# Sheet1.net
KiCad netlist of a schematic drawn in Altium Designer
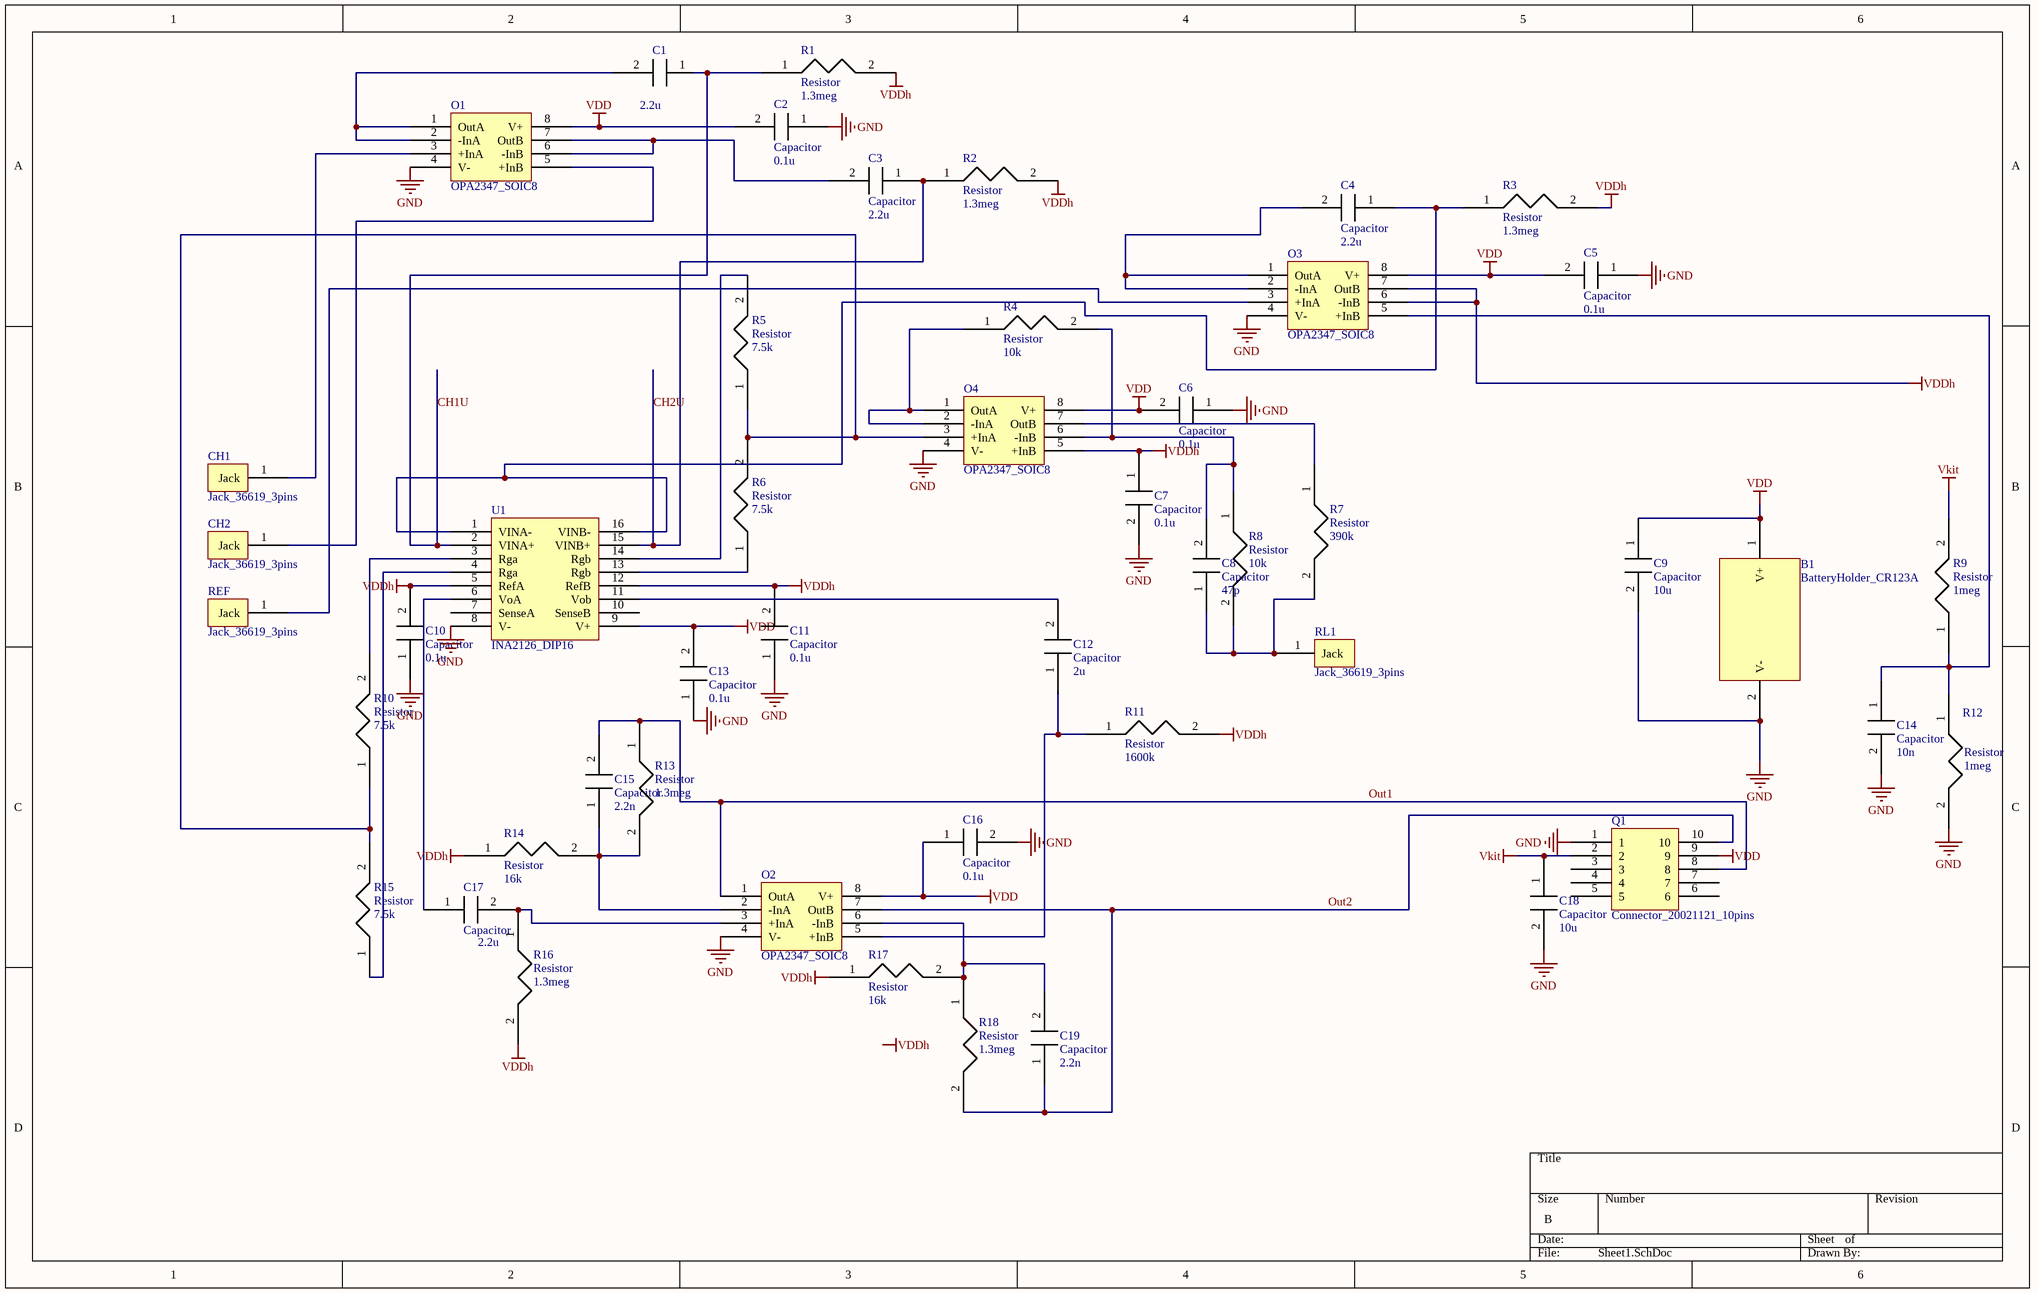
[diagram p0: Sheet1.SchDoc]

(export (version "E")
  (design (tool "Eeschema 10.0.6"))
  (components
    (comp (ref "B1")
      (value "BatteryHolder_CR123A")
      (footprint "BatterHolder_CR123A")
      (libsource (lib "Schlib1") (part "BatteryHolder_CR123A"))
    )
    (comp (ref "C1")
      (value "2.2u")
      (footprint "Capacitor")
      (fields (field (name "Comment") "Capacitor"))
      (libsource (lib "Schlib1") (part "Capacitor"))
    )
    (comp (ref "C2")
      (value "Capacitor")
      (footprint "Capacitor")
      (fields (field (name "ALTIUM_VALUE") "0.1u"))
      (libsource (lib "Schlib1") (part "Capacitor"))
    )
    (comp (ref "C3")
      (value "Capacitor")
      (footprint "Capacitor")
      (fields (field (name "ALTIUM_VALUE") "2.2u"))
      (libsource (lib "Schlib1") (part "Capacitor"))
    )
    (comp (ref "C4")
      (value "Capacitor")
      (footprint "Capacitor")
      (fields (field (name "ALTIUM_VALUE") "2.2u"))
      (libsource (lib "Schlib1") (part "Capacitor"))
    )
    (comp (ref "C5")
      (value "Capacitor")
      (footprint "Capacitor")
      (fields (field (name "ALTIUM_VALUE") "0.1u"))
      (libsource (lib "Schlib1") (part "Capacitor"))
    )
    (comp (ref "C6")
      (value "Capacitor")
      (footprint "Capacitor")
      (fields (field (name "ALTIUM_VALUE") "0.1u"))
      (libsource (lib "Schlib1") (part "Capacitor"))
    )
    (comp (ref "C7")
      (value "Capacitor")
      (footprint "Capacitor")
      (fields (field (name "ALTIUM_VALUE") "0.1u"))
      (libsource (lib "Schlib1") (part "Capacitor"))
    )
    (comp (ref "C8")
      (value "Capacitor")
      (footprint "Capacitor")
      (fields (field (name "ALTIUM_VALUE") "47p"))
      (libsource (lib "Schlib1") (part "Capacitor"))
    )
    (comp (ref "C9")
      (value "Capacitor")
      (footprint "Capacitor")
      (fields (field (name "ALTIUM_VALUE") "10u"))
      (libsource (lib "Schlib1") (part "Capacitor"))
    )
    (comp (ref "C10")
      (value "Capacitor")
      (footprint "Capacitor")
      (fields (field (name "ALTIUM_VALUE") "0.1u"))
      (libsource (lib "Schlib1") (part "Capacitor"))
    )
    (comp (ref "C11")
      (value "Capacitor")
      (footprint "Capacitor")
      (fields (field (name "ALTIUM_VALUE") "0.1u"))
      (libsource (lib "Schlib1") (part "Capacitor"))
    )
    (comp (ref "C12")
      (value "Capacitor")
      (footprint "Capacitor")
      (fields (field (name "ALTIUM_VALUE") "2u"))
      (libsource (lib "Schlib1") (part "Capacitor"))
    )
    (comp (ref "C13")
      (value "Capacitor")
      (footprint "Capacitor")
      (fields (field (name "ALTIUM_VALUE") "0.1u"))
      (libsource (lib "Schlib1") (part "Capacitor"))
    )
    (comp (ref "C14")
      (value "Capacitor")
      (footprint "Capacitor")
      (fields (field (name "ALTIUM_VALUE") "10n"))
      (libsource (lib "Schlib1") (part "Capacitor"))
    )
    (comp (ref "C15")
      (value "Capacitor")
      (footprint "Capacitor")
      (fields (field (name "ALTIUM_VALUE") "2.2n"))
      (libsource (lib "Schlib1") (part "Capacitor"))
    )
    (comp (ref "C16")
      (value "Capacitor")
      (footprint "Capacitor")
      (fields (field (name "ALTIUM_VALUE") "0.1u"))
      (libsource (lib "Schlib1") (part "Capacitor"))
    )
    (comp (ref "C17")
      (value "Capacitor")
      (footprint "Capacitor")
      (fields (field (name "ALTIUM_VALUE") "2.2u"))
      (libsource (lib "Schlib1") (part "Capacitor"))
    )
    (comp (ref "C18")
      (value "Capacitor")
      (footprint "Capacitor")
      (fields (field (name "ALTIUM_VALUE") "10u"))
      (libsource (lib "Schlib1") (part "Capacitor"))
    )
    (comp (ref "C19")
      (value "Capacitor")
      (footprint "Capacitor")
      (fields (field (name "ALTIUM_VALUE") "2.2n"))
      (libsource (lib "Schlib1") (part "Capacitor"))
    )
    (comp (ref "CH1")
      (value "Jack_36619_3pins")
      (footprint "Jack_36619_3pads")
      (libsource (lib "Schlib1") (part "Jack_36619_3pins"))
    )
    (comp (ref "CH2")
      (value "Jack_36619_3pins")
      (footprint "Jack_36619_3pads")
      (libsource (lib "Schlib1") (part "Jack_36619_3pins"))
    )
    (comp (ref "O1")
      (value "OPA2347_SOIC8")
      (footprint "OPA2347P_SOIC8")
      (libsource (lib "Schlib1") (part "OPA2347_SOIC8"))
    )
    (comp (ref "O2")
      (value "OPA2347_SOIC8")
      (footprint "OPA2347P_SOIC8")
      (libsource (lib "Schlib1") (part "OPA2347_SOIC8"))
    )
    (comp (ref "O3")
      (value "OPA2347_SOIC8")
      (footprint "OPA2347P_SOIC8")
      (libsource (lib "Schlib1") (part "OPA2347_SOIC8"))
    )
    (comp (ref "O4")
      (value "OPA2347_SOIC8")
      (footprint "OPA2347P_SOIC8")
      (libsource (lib "Schlib1") (part "OPA2347_SOIC8"))
    )
    (comp (ref "Q1")
      (value "Connector_20021121_10pins")
      (footprint "20021121-10pins")
      (libsource (lib "Schlib1") (part "Connector_20021121_10pins"))
    )
    (comp (ref "R1")
      (value "Resistor")
      (footprint "Resisitor")
      (fields (field (name "ALTIUM_VALUE") "1.3meg"))
      (libsource (lib "Schlib1") (part "Resistor"))
    )
    (comp (ref "R2")
      (value "Resistor")
      (footprint "Resisitor")
      (fields (field (name "ALTIUM_VALUE") "1.3meg"))
      (libsource (lib "Schlib1") (part "Resistor"))
    )
    (comp (ref "R3")
      (value "Resistor")
      (footprint "Resisitor")
      (fields (field (name "ALTIUM_VALUE") "1.3meg"))
      (libsource (lib "Schlib1") (part "Resistor"))
    )
    (comp (ref "R4")
      (value "Resistor")
      (footprint "Resisitor")
      (fields (field (name "ALTIUM_VALUE") "10k"))
      (libsource (lib "Schlib1") (part "Resistor"))
    )
    (comp (ref "R5")
      (value "Resistor")
      (footprint "Resisitor")
      (fields (field (name "ALTIUM_VALUE") "7.5k"))
      (libsource (lib "Schlib1") (part "Resistor"))
    )
    (comp (ref "R6")
      (value "Resistor")
      (footprint "Resisitor")
      (fields (field (name "ALTIUM_VALUE") "7.5k"))
      (libsource (lib "Schlib1") (part "Resistor"))
    )
    (comp (ref "R7")
      (value "Resistor")
      (footprint "Resisitor")
      (fields (field (name "ALTIUM_VALUE") "390k"))
      (libsource (lib "Schlib1") (part "Resistor"))
    )
    (comp (ref "R8")
      (value "Resistor")
      (footprint "Resisitor")
      (fields (field (name "ALTIUM_VALUE") "10k"))
      (libsource (lib "Schlib1") (part "Resistor"))
    )
    (comp (ref "R9")
      (value "Resistor")
      (footprint "Resisitor")
      (fields (field (name "ALTIUM_VALUE") "1meg"))
      (libsource (lib "Schlib1") (part "Resistor"))
    )
    (comp (ref "R10")
      (value "Resistor")
      (footprint "Resisitor")
      (fields (field (name "ALTIUM_VALUE") "7.5k"))
      (libsource (lib "Schlib1") (part "Resistor"))
    )
    (comp (ref "R11")
      (value "Resistor")
      (footprint "Resisitor")
      (fields (field (name "ALTIUM_VALUE") "1600k"))
      (libsource (lib "Schlib1") (part "Resistor"))
    )
    (comp (ref "R12")
      (value "Resistor")
      (footprint "Resisitor")
      (fields (field (name "ALTIUM_VALUE") "1meg"))
      (libsource (lib "Schlib1") (part "Resistor"))
    )
    (comp (ref "R13")
      (value "Resistor")
      (footprint "Resisitor")
      (fields (field (name "ALTIUM_VALUE") "1.3meg"))
      (libsource (lib "Schlib1") (part "Resistor"))
    )
    (comp (ref "R14")
      (value "Resistor")
      (footprint "Resisitor")
      (fields (field (name "ALTIUM_VALUE") "16k"))
      (libsource (lib "Schlib1") (part "Resistor"))
    )
    (comp (ref "R15")
      (value "Resistor")
      (footprint "Resisitor")
      (fields (field (name "ALTIUM_VALUE") "7.5k"))
      (libsource (lib "Schlib1") (part "Resistor"))
    )
    (comp (ref "R16")
      (value "Resistor")
      (footprint "Resisitor")
      (fields (field (name "ALTIUM_VALUE") "1.3meg"))
      (libsource (lib "Schlib1") (part "Resistor"))
    )
    (comp (ref "R17")
      (value "Resistor")
      (footprint "Resisitor")
      (fields (field (name "ALTIUM_VALUE") "16k"))
      (libsource (lib "Schlib1") (part "Resistor"))
    )
    (comp (ref "R18")
      (value "Resistor")
      (footprint "Resisitor")
      (fields (field (name "ALTIUM_VALUE") "1.3meg"))
      (libsource (lib "Schlib1") (part "Resistor"))
    )
    (comp (ref "REF")
      (value "Jack_36619_3pins")
      (footprint "Jack_36619_3pads")
      (libsource (lib "Schlib1") (part "Jack_36619_3pins"))
    )
    (comp (ref "RL1")
      (value "Jack_36619_3pins")
      (footprint "Jack_36619_3pads")
      (libsource (lib "") (part "Jack_36619_3pins_1"))
    )
    (comp (ref "U1")
      (value "INA2126_DIP16")
      (footprint "INA2126_DIP16")
      (libsource (lib "Schlib1") (part "INA2126_DIP16"))
    )
  )
  (nets
    (net (code "1") (name "/CH1U") (class "Default")
      (node (ref "C1") (pin "1") (pinfunction "V-_1") (pintype "passive"))
      (node (ref "R1") (pin "1") (pinfunction "V-_1") (pintype "passive"))
      (node (ref "U1") (pin "2") (pinfunction "VINA+_2") (pintype "passive"))
    )
    (net (code "2") (name "/CH2U") (class "Default")
      (node (ref "C3") (pin "1") (pinfunction "V-_1") (pintype "passive"))
      (node (ref "R2") (pin "1") (pinfunction "V-_1") (pintype "passive"))
      (node (ref "U1") (pin "15") (pinfunction "VINB+_15") (pintype "passive"))
    )
    (net (code "3") (name "/Out1") (class "Default")
      (node (ref "C15") (pin "2") (pinfunction "V-_2") (pintype "passive"))
      (node (ref "O2") (pin "1") (pinfunction "OutA_1") (pintype "passive"))
      (node (ref "Q1") (pin "8") (pinfunction "8_8") (pintype "passive"))
      (node (ref "R13") (pin "1") (pinfunction "V-_1") (pintype "passive"))
    )
    (net (code "4") (name "/Out2") (class "Default")
      (node (ref "C19") (pin "1") (pinfunction "V-_1") (pintype "passive"))
      (node (ref "O2") (pin "7") (pinfunction "OutB_7") (pintype "passive"))
      (node (ref "Q1") (pin "10") (pinfunction "10_10") (pintype "passive"))
      (node (ref "R18") (pin "2") (pinfunction "V-_2") (pintype "passive"))
    )
    (net (code "5") (name "GND") (class "Default")
      (node (ref "B1") (pin "2") (pinfunction "V-_2") (pintype "passive"))
      (node (ref "C10") (pin "1") (pinfunction "V-_1") (pintype "passive"))
      (node (ref "C11") (pin "1") (pinfunction "V-_1") (pintype "passive"))
      (node (ref "C13") (pin "1") (pinfunction "V-_1") (pintype "passive"))
      (node (ref "C14") (pin "2") (pinfunction "V-_2") (pintype "passive"))
      (node (ref "C16") (pin "2") (pinfunction "V-_2") (pintype "passive"))
      (node (ref "C18") (pin "2") (pinfunction "V-_2") (pintype "passive"))
      (node (ref "C2") (pin "1") (pinfunction "V-_1") (pintype "passive"))
      (node (ref "C5") (pin "1") (pinfunction "V-_1") (pintype "passive"))
      (node (ref "C6") (pin "1") (pinfunction "V-_1") (pintype "passive"))
      (node (ref "C7") (pin "2") (pinfunction "V-_2") (pintype "passive"))
      (node (ref "C9") (pin "2") (pinfunction "V-_2") (pintype "passive"))
      (node (ref "O1") (pin "4") (pinfunction "V-_4") (pintype "passive"))
      (node (ref "O2") (pin "4") (pinfunction "V-_4") (pintype "passive"))
      (node (ref "O3") (pin "4") (pinfunction "V-_4") (pintype "passive"))
      (node (ref "O4") (pin "4") (pinfunction "V-_4") (pintype "passive"))
      (node (ref "Q1") (pin "1") (pinfunction "1_1") (pintype "passive"))
      (node (ref "R12") (pin "2") (pinfunction "V-_2") (pintype "passive"))
      (node (ref "U1") (pin "8") (pinfunction "V-_8") (pintype "passive"))
    )
    (net (code "6") (name "Net-(CH1-Jack)") (class "Default")
      (node (ref "CH1") (pin "1") (pinfunction "Jack_1") (pintype "passive"))
      (node (ref "O1") (pin "3") (pinfunction "+InA_3") (pintype "passive"))
    )
    (net (code "7") (name "Net-(CH2-Jack)") (class "Default")
      (node (ref "CH2") (pin "1") (pinfunction "Jack_1") (pintype "passive"))
      (node (ref "O1") (pin "5") (pinfunction "+InB_5") (pintype "passive"))
    )
    (net (code "8") (name "Net-(O1--InA)") (class "Default")
      (node (ref "C1") (pin "2") (pinfunction "V-_2") (pintype "passive"))
      (node (ref "O1") (pin "1") (pinfunction "OutA_1") (pintype "passive"))
      (node (ref "O1") (pin "2") (pinfunction "-InA_2") (pintype "passive"))
    )
    (net (code "9") (name "Net-(O1--InB)") (class "Default")
      (node (ref "C3") (pin "2") (pinfunction "V-_2") (pintype "passive"))
      (node (ref "O1") (pin "6") (pinfunction "-InB_6") (pintype "passive"))
      (node (ref "O1") (pin "7") (pinfunction "OutB_7") (pintype "passive"))
    )
    (net (code "10") (name "Net-(O2-+InA)") (class "Default")
      (node (ref "C17") (pin "2") (pinfunction "V-_2") (pintype "passive"))
      (node (ref "O2") (pin "3") (pinfunction "+InA_3") (pintype "passive"))
      (node (ref "R16") (pin "1") (pinfunction "V-_1") (pintype "passive"))
    )
    (net (code "11") (name "Net-(O2-+InB)") (class "Default")
      (node (ref "C12") (pin "1") (pinfunction "V-_1") (pintype "passive"))
      (node (ref "O2") (pin "5") (pinfunction "+InB_5") (pintype "passive"))
      (node (ref "R11") (pin "1") (pinfunction "V-_1") (pintype "passive"))
    )
    (net (code "12") (name "Net-(O2--InA)") (class "Default")
      (node (ref "C15") (pin "1") (pinfunction "V-_1") (pintype "passive"))
      (node (ref "O2") (pin "2") (pinfunction "-InA_2") (pintype "passive"))
      (node (ref "R13") (pin "2") (pinfunction "V-_2") (pintype "passive"))
      (node (ref "R14") (pin "2") (pinfunction "V-_2") (pintype "passive"))
    )
    (net (code "13") (name "Net-(O2--InB)") (class "Default")
      (node (ref "C19") (pin "2") (pinfunction "V-_2") (pintype "passive"))
      (node (ref "O2") (pin "6") (pinfunction "-InB_6") (pintype "passive"))
      (node (ref "R17") (pin "2") (pinfunction "V-_2") (pintype "passive"))
      (node (ref "R18") (pin "1") (pinfunction "V-_1") (pintype "passive"))
    )
    (net (code "14") (name "Net-(O3-+InA)") (class "Default")
      (node (ref "O3") (pin "3") (pinfunction "+InA_3") (pintype "passive"))
      (node (ref "REF") (pin "1") (pinfunction "Jack_1") (pintype "passive"))
    )
    (net (code "15") (name "Net-(O3-+InB)") (class "Default")
      (node (ref "C14") (pin "1") (pinfunction "V-_1") (pintype "passive"))
      (node (ref "O3") (pin "5") (pinfunction "+InB_5") (pintype "passive"))
      (node (ref "R12") (pin "1") (pinfunction "V-_1") (pintype "passive"))
      (node (ref "R9") (pin "1") (pinfunction "V-_1") (pintype "passive"))
    )
    (net (code "16") (name "Net-(O3--InA)") (class "Default")
      (node (ref "C4") (pin "2") (pinfunction "V-_2") (pintype "passive"))
      (node (ref "O3") (pin "1") (pinfunction "OutA_1") (pintype "passive"))
      (node (ref "O3") (pin "2") (pinfunction "-InA_2") (pintype "passive"))
    )
    (net (code "17") (name "Net-(O4-+InA)") (class "Default")
      (node (ref "O4") (pin "3") (pinfunction "+InA_3") (pintype "passive"))
      (node (ref "R10") (pin "1") (pinfunction "V-_1") (pintype "passive"))
      (node (ref "R15") (pin "2") (pinfunction "V-_2") (pintype "passive"))
      (node (ref "R5") (pin "1") (pinfunction "V-_1") (pintype "passive"))
      (node (ref "R6") (pin "2") (pinfunction "V-_2") (pintype "passive"))
    )
    (net (code "18") (name "Net-(O4--InA)") (class "Default")
      (node (ref "O4") (pin "1") (pinfunction "OutA_1") (pintype "passive"))
      (node (ref "O4") (pin "2") (pinfunction "-InA_2") (pintype "passive"))
      (node (ref "R4") (pin "1") (pinfunction "V-_1") (pintype "passive"))
    )
    (net (code "19") (name "Net-(O4--InB)") (class "Default")
      (node (ref "C8") (pin "2") (pinfunction "V-_2") (pintype "passive"))
      (node (ref "O4") (pin "6") (pinfunction "-InB_6") (pintype "passive"))
      (node (ref "R4") (pin "2") (pinfunction "V-_2") (pintype "passive"))
      (node (ref "R8") (pin "1") (pinfunction "V-_1") (pintype "passive"))
    )
    (net (code "20") (name "Net-(O4-OutB)") (class "Default")
      (node (ref "O4") (pin "7") (pinfunction "OutB_7") (pintype "passive"))
      (node (ref "R7") (pin "1") (pinfunction "V-_1") (pintype "passive"))
    )
    (net (code "21") (name "Net-(R5-V--Pad2)") (class "Default")
      (node (ref "R5") (pin "2") (pinfunction "V-_2") (pintype "passive"))
      (node (ref "U1") (pin "14") (pinfunction "Rgb_14") (pintype "passive"))
    )
    (net (code "22") (name "Net-(R6-V--Pad1)") (class "Default")
      (node (ref "R6") (pin "1") (pinfunction "V-_1") (pintype "passive"))
      (node (ref "U1") (pin "13") (pinfunction "Rgb_13") (pintype "passive"))
    )
    (net (code "23") (name "Net-(R10-V--Pad2)") (class "Default")
      (node (ref "R10") (pin "2") (pinfunction "V-_2") (pintype "passive"))
      (node (ref "U1") (pin "3") (pinfunction "Rga_3") (pintype "passive"))
    )
    (net (code "24") (name "Net-(R15-V--Pad1)") (class "Default")
      (node (ref "R15") (pin "1") (pinfunction "V-_1") (pintype "passive"))
      (node (ref "U1") (pin "4") (pinfunction "Rga_4") (pintype "passive"))
    )
    (net (code "25") (name "Net-(RL1-Jack)") (class "Default")
      (node (ref "C8") (pin "1") (pinfunction "V-_1") (pintype "passive"))
      (node (ref "R7") (pin "2") (pinfunction "V-_2") (pintype "passive"))
      (node (ref "R8") (pin "2") (pinfunction "V-_2") (pintype "passive"))
      (node (ref "RL1") (pin "1") (pinfunction "Jack_1") (pintype "passive"))
    )
    (net (code "26") (name "Net-(U1-VINA-)") (class "Default")
      (node (ref "C4") (pin "1") (pinfunction "V-_1") (pintype "passive"))
      (node (ref "R3") (pin "1") (pinfunction "V-_1") (pintype "passive"))
      (node (ref "U1") (pin "1") (pinfunction "VINA-_1") (pintype "passive"))
      (node (ref "U1") (pin "16") (pinfunction "VINB-_16") (pintype "passive"))
    )
    (net (code "27") (name "Net-(U1-VoA)") (class "Default")
      (node (ref "C17") (pin "1") (pinfunction "V-_1") (pintype "passive"))
      (node (ref "U1") (pin "6") (pinfunction "VoA_6") (pintype "passive"))
    )
    (net (code "28") (name "Net-(U1-Vob)") (class "Default")
      (node (ref "C12") (pin "2") (pinfunction "V-_2") (pintype "passive"))
      (node (ref "U1") (pin "11") (pinfunction "Vob_11") (pintype "passive"))
    )
    (net (code "29") (name "VDD") (class "Default")
      (node (ref "B1") (pin "1") (pinfunction "V+_1") (pintype "passive"))
      (node (ref "C13") (pin "2") (pinfunction "V-_2") (pintype "passive"))
      (node (ref "C16") (pin "1") (pinfunction "V-_1") (pintype "passive"))
      (node (ref "C2") (pin "2") (pinfunction "V-_2") (pintype "passive"))
      (node (ref "C5") (pin "2") (pinfunction "V-_2") (pintype "passive"))
      (node (ref "C6") (pin "2") (pinfunction "V-_2") (pintype "passive"))
      (node (ref "C9") (pin "1") (pinfunction "V-_1") (pintype "passive"))
      (node (ref "O1") (pin "8") (pinfunction "V+_8") (pintype "passive"))
      (node (ref "O2") (pin "8") (pinfunction "V+_8") (pintype "passive"))
      (node (ref "O3") (pin "8") (pinfunction "V+_8") (pintype "passive"))
      (node (ref "O4") (pin "8") (pinfunction "V+_8") (pintype "passive"))
      (node (ref "Q1") (pin "9") (pinfunction "9_9") (pintype "passive"))
      (node (ref "U1") (pin "9") (pinfunction "V+_9") (pintype "passive"))
    )
    (net (code "30") (name "VDDh") (class "Default")
      (node (ref "C10") (pin "2") (pinfunction "V-_2") (pintype "passive"))
      (node (ref "C11") (pin "2") (pinfunction "V-_2") (pintype "passive"))
      (node (ref "C7") (pin "1") (pinfunction "V-_1") (pintype "passive"))
      (node (ref "O3") (pin "6") (pinfunction "-InB_6") (pintype "passive"))
      (node (ref "O3") (pin "7") (pinfunction "OutB_7") (pintype "passive"))
      (node (ref "O4") (pin "5") (pinfunction "+InB_5") (pintype "passive"))
      (node (ref "R1") (pin "2") (pinfunction "V-_2") (pintype "passive"))
      (node (ref "R11") (pin "2") (pinfunction "V-_2") (pintype "passive"))
      (node (ref "R14") (pin "1") (pinfunction "V-_1") (pintype "passive"))
      (node (ref "R16") (pin "2") (pinfunction "V-_2") (pintype "passive"))
      (node (ref "R17") (pin "1") (pinfunction "V-_1") (pintype "passive"))
      (node (ref "R2") (pin "2") (pinfunction "V-_2") (pintype "passive"))
      (node (ref "R3") (pin "2") (pinfunction "V-_2") (pintype "passive"))
      (node (ref "U1") (pin "12") (pinfunction "RefB_12") (pintype "passive"))
      (node (ref "U1") (pin "5") (pinfunction "RefA_5") (pintype "passive"))
    )
    (net (code "31") (name "Vkit") (class "Default")
      (node (ref "C18") (pin "1") (pinfunction "V-_1") (pintype "passive"))
      (node (ref "Q1") (pin "2") (pinfunction "2_2") (pintype "passive"))
      (node (ref "R9") (pin "2") (pinfunction "V-_2") (pintype "passive"))
    )
    (net (code "32") (name "unconnected-(Q1-Pad3)") (class "Default")
      (node (ref "Q1") (pin "3") (pinfunction "3_3") (pintype "passive"))
    )
    (net (code "33") (name "unconnected-(Q1-Pad4)") (class "Default")
      (node (ref "Q1") (pin "4") (pinfunction "4_4") (pintype "passive"))
    )
    (net (code "34") (name "unconnected-(Q1-Pad5)") (class "Default")
      (node (ref "Q1") (pin "5") (pinfunction "5_5") (pintype "passive"))
    )
    (net (code "35") (name "unconnected-(Q1-Pad6)") (class "Default")
      (node (ref "Q1") (pin "6") (pinfunction "6_6") (pintype "passive"))
    )
    (net (code "36") (name "unconnected-(Q1-Pad7)") (class "Default")
      (node (ref "Q1") (pin "7") (pinfunction "7_7") (pintype "passive"))
    )
    (net (code "37") (name "unconnected-(U1-SenseA-Pad7)") (class "Default")
      (node (ref "U1") (pin "7") (pinfunction "SenseA_7") (pintype "passive"))
    )
    (net (code "38") (name "unconnected-(U1-SenseB-Pad10)") (class "Default")
      (node (ref "U1") (pin "10") (pinfunction "SenseB_10") (pintype "passive"))
    )
  )
)
